# MAIN_GPS.net
KiCad netlist of a schematic drawn in Altium Designer
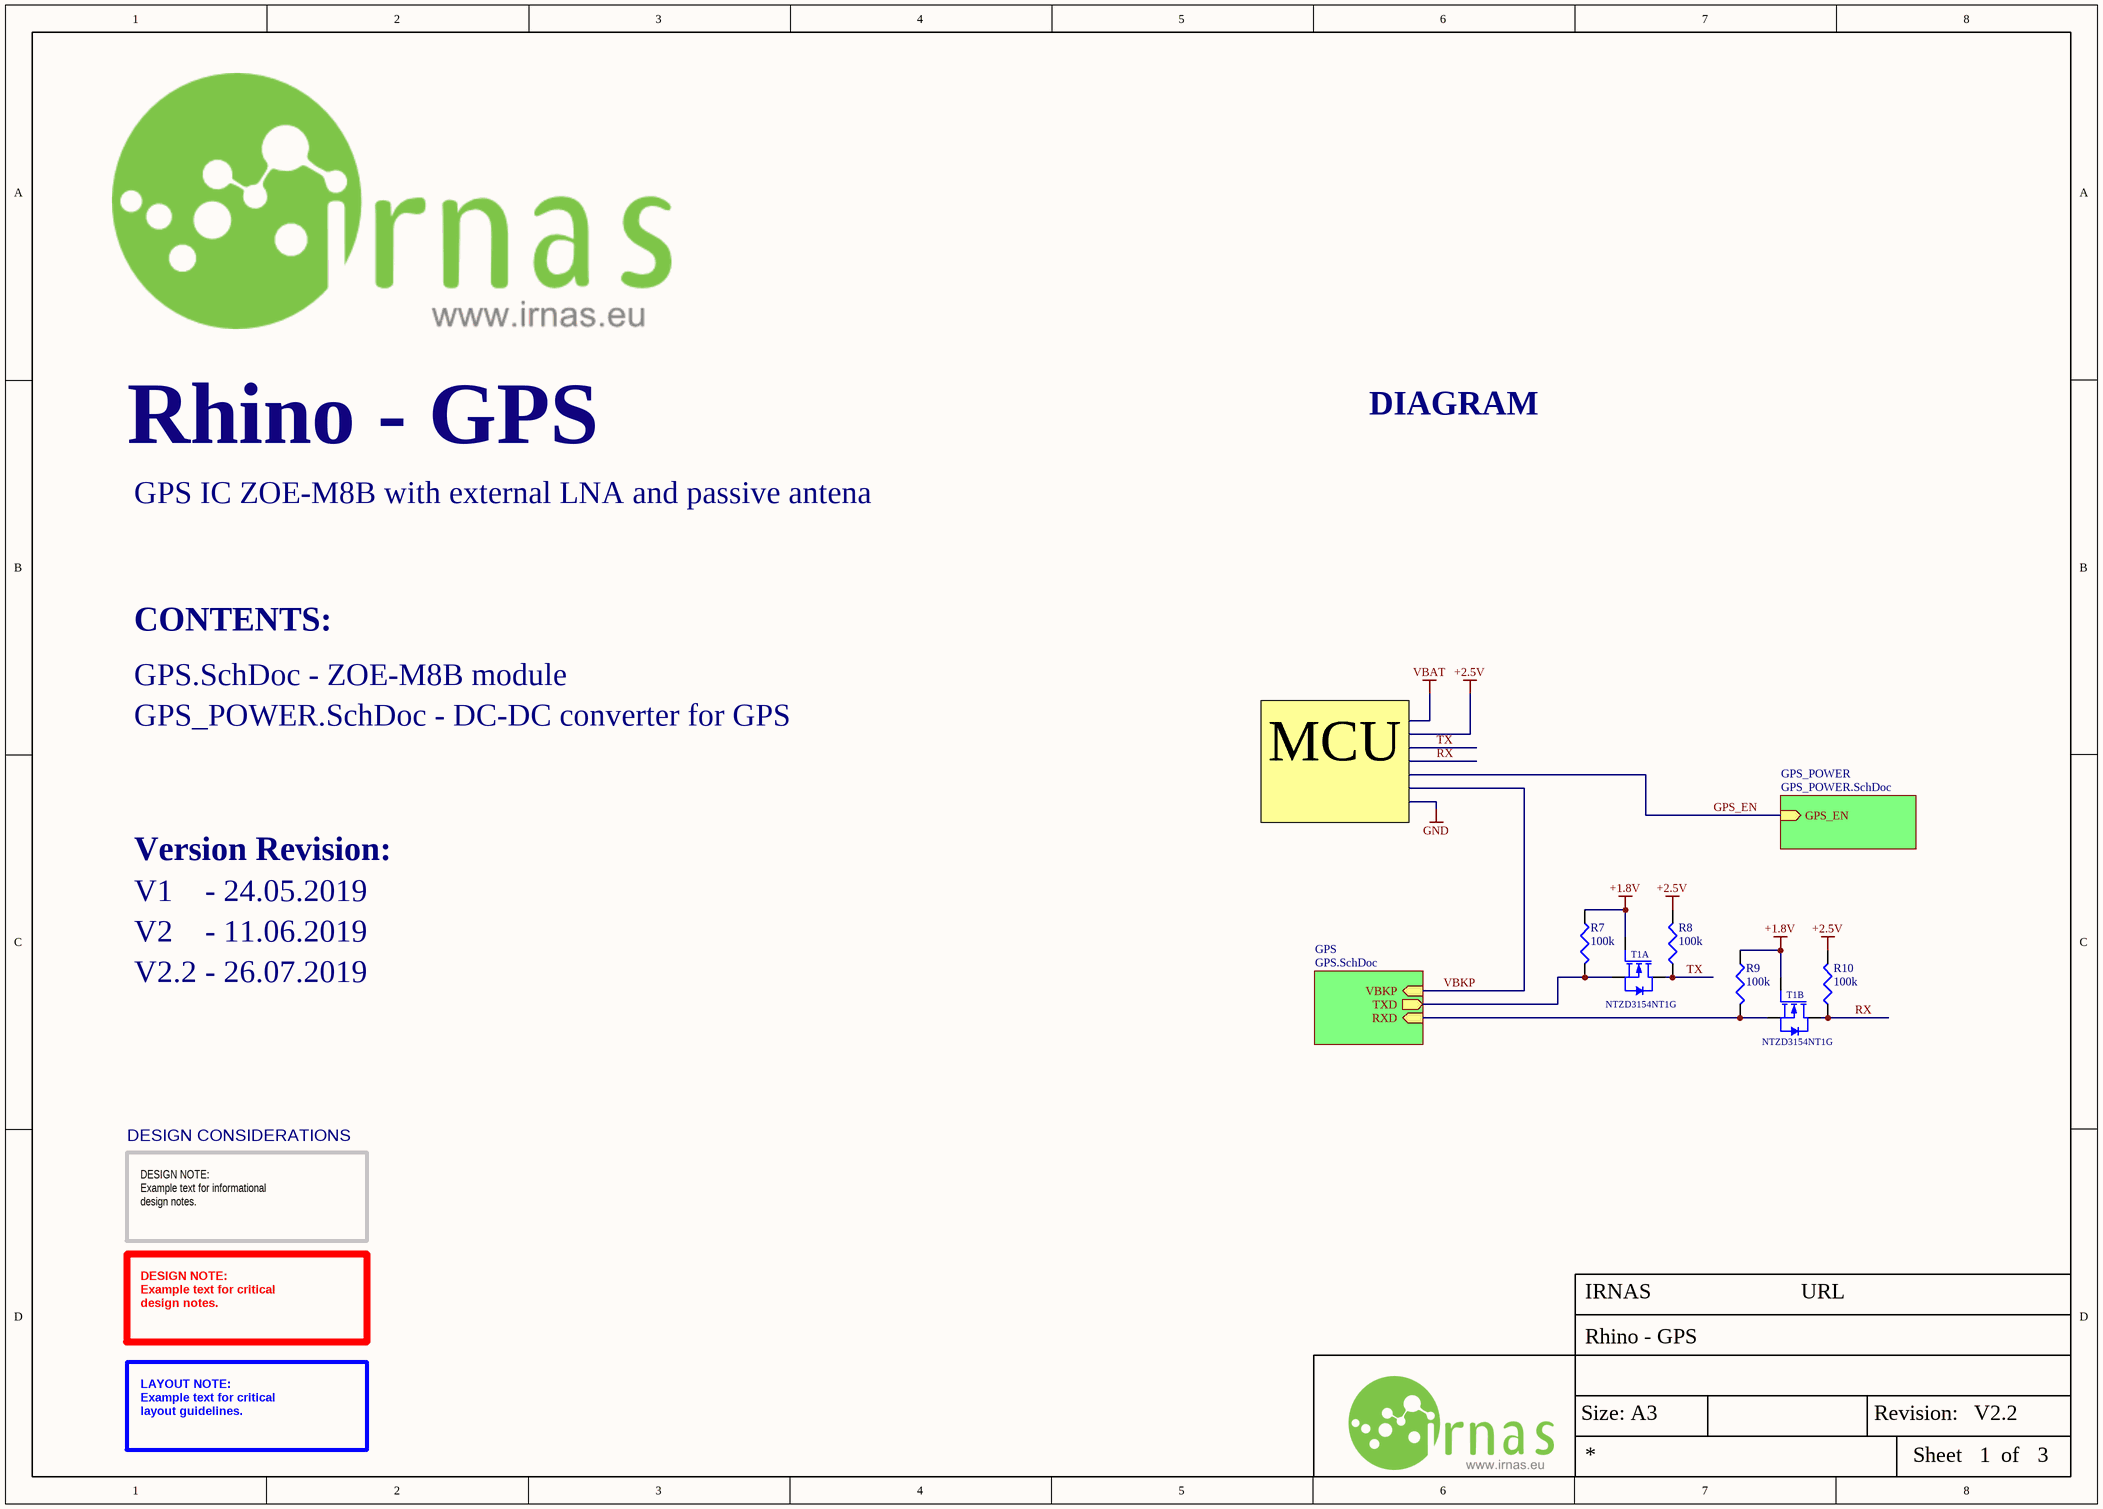
[diagram p0: MAIN_GPS.SchDoc]

(export (version "E")
  (design (tool "Eeschema 10.0.6"))
  (components
    (comp (ref "R7")
      (value "100k")
      (footprint "RES0402")
      (description "MULTICOMP   MCWR04X1003FTL   RES, THICK FILM, 100KOHM, 1%, 0.0625W")
      (fields
        (field (name "MANUFACTURER") "Multicomp")
        (field (name "MANUFACTURER PART NUMBER") "MCWR04X1003FTL")
      )
      (libsource (lib "Passive") (part "R - 100k/0402"))
    )
    (comp (ref "R8")
      (value "100k")
      (footprint "RES0402")
      (description "MULTICOMP   MCWR04X1003FTL   RES, THICK FILM, 100KOHM, 1%, 0.0625W")
      (fields
        (field (name "MANUFACTURER") "Multicomp")
        (field (name "MANUFACTURER PART NUMBER") "MCWR04X1003FTL")
      )
      (libsource (lib "Passive") (part "R - 100k/0402"))
    )
    (comp (ref "R9")
      (value "100k")
      (footprint "RES0402")
      (description "MULTICOMP   MCWR04X1003FTL   RES, THICK FILM, 100KOHM, 1%, 0.0625W")
      (fields
        (field (name "MANUFACTURER") "Multicomp")
        (field (name "MANUFACTURER PART NUMBER") "MCWR04X1003FTL")
      )
      (libsource (lib "Passive") (part "R - 100k/0402"))
    )
    (comp (ref "R10")
      (value "100k")
      (footprint "RES0402")
      (description "MULTICOMP   MCWR04X1003FTL   RES, THICK FILM, 100KOHM, 1%, 0.0625W")
      (fields
        (field (name "MANUFACTURER") "Multicomp")
        (field (name "MANUFACTURER PART NUMBER") "MCWR04X1003FTL")
      )
      (libsource (lib "Passive") (part "R - 100k/0402"))
    )
    (comp (ref "T1")
      (value "NTZD3154NT1G")
      (footprint "SOT-563")
      (description "Dual MOSFET, Dual N Channel, 540 mA, 20 V, 0.4 ohm, 4.5 V, 1 V")
      (fields (field (name "AUTHOR") "Ciril Golob"))
      (libsource (lib "Active") (part "T_M - NTZD3154NT1G"))
    )
  )
  (nets
    (net (code "1") (name "+1.8V") (class "Default")
      (node (ref "R7") (pin "1") (pinfunction "1_1") (pintype "passive"))
      (node (ref "R9") (pin "1") (pinfunction "1_1") (pintype "passive"))
      (node (ref "T1") (pin "2") (pinfunction "G1_2") (pintype "passive"))
      (node (ref "T1") (pin "5") (pinfunction "G2_5") (pintype "passive"))
    )
    (net (code "2") (name "+2.5V") (class "Default")
      (node (ref "R10") (pin "2") (pinfunction "2_2") (pintype "passive"))
      (node (ref "R8") (pin "2") (pinfunction "2_2") (pintype "passive"))
    )
    (net (code "4") (name "/RX") (class "Default")
      (node (ref "R10") (pin "1") (pinfunction "1_1") (pintype "passive"))
      (node (ref "T1") (pin "3") (pinfunction "D2_3") (pintype "passive"))
    )
    (net (code "5") (name "/RXD") (class "Default")
      (node (ref "R9") (pin "2") (pinfunction "2_2") (pintype "passive"))
      (node (ref "T1") (pin "4") (pinfunction "S2_4") (pintype "passive"))
    )
    (net (code "6") (name "/TX") (class "Default")
      (node (ref "R8") (pin "1") (pinfunction "1_1") (pintype "passive"))
      (node (ref "T1") (pin "6") (pinfunction "D1_6") (pintype "passive"))
    )
    (net (code "7") (name "/TXD") (class "Default")
      (node (ref "R7") (pin "2") (pinfunction "2_2") (pintype "passive"))
      (node (ref "T1") (pin "1") (pinfunction "S1_1") (pintype "passive"))
    )
  )
)
